# gyro_adxr.net
KiCad netlist of a schematic drawn in EAGLE
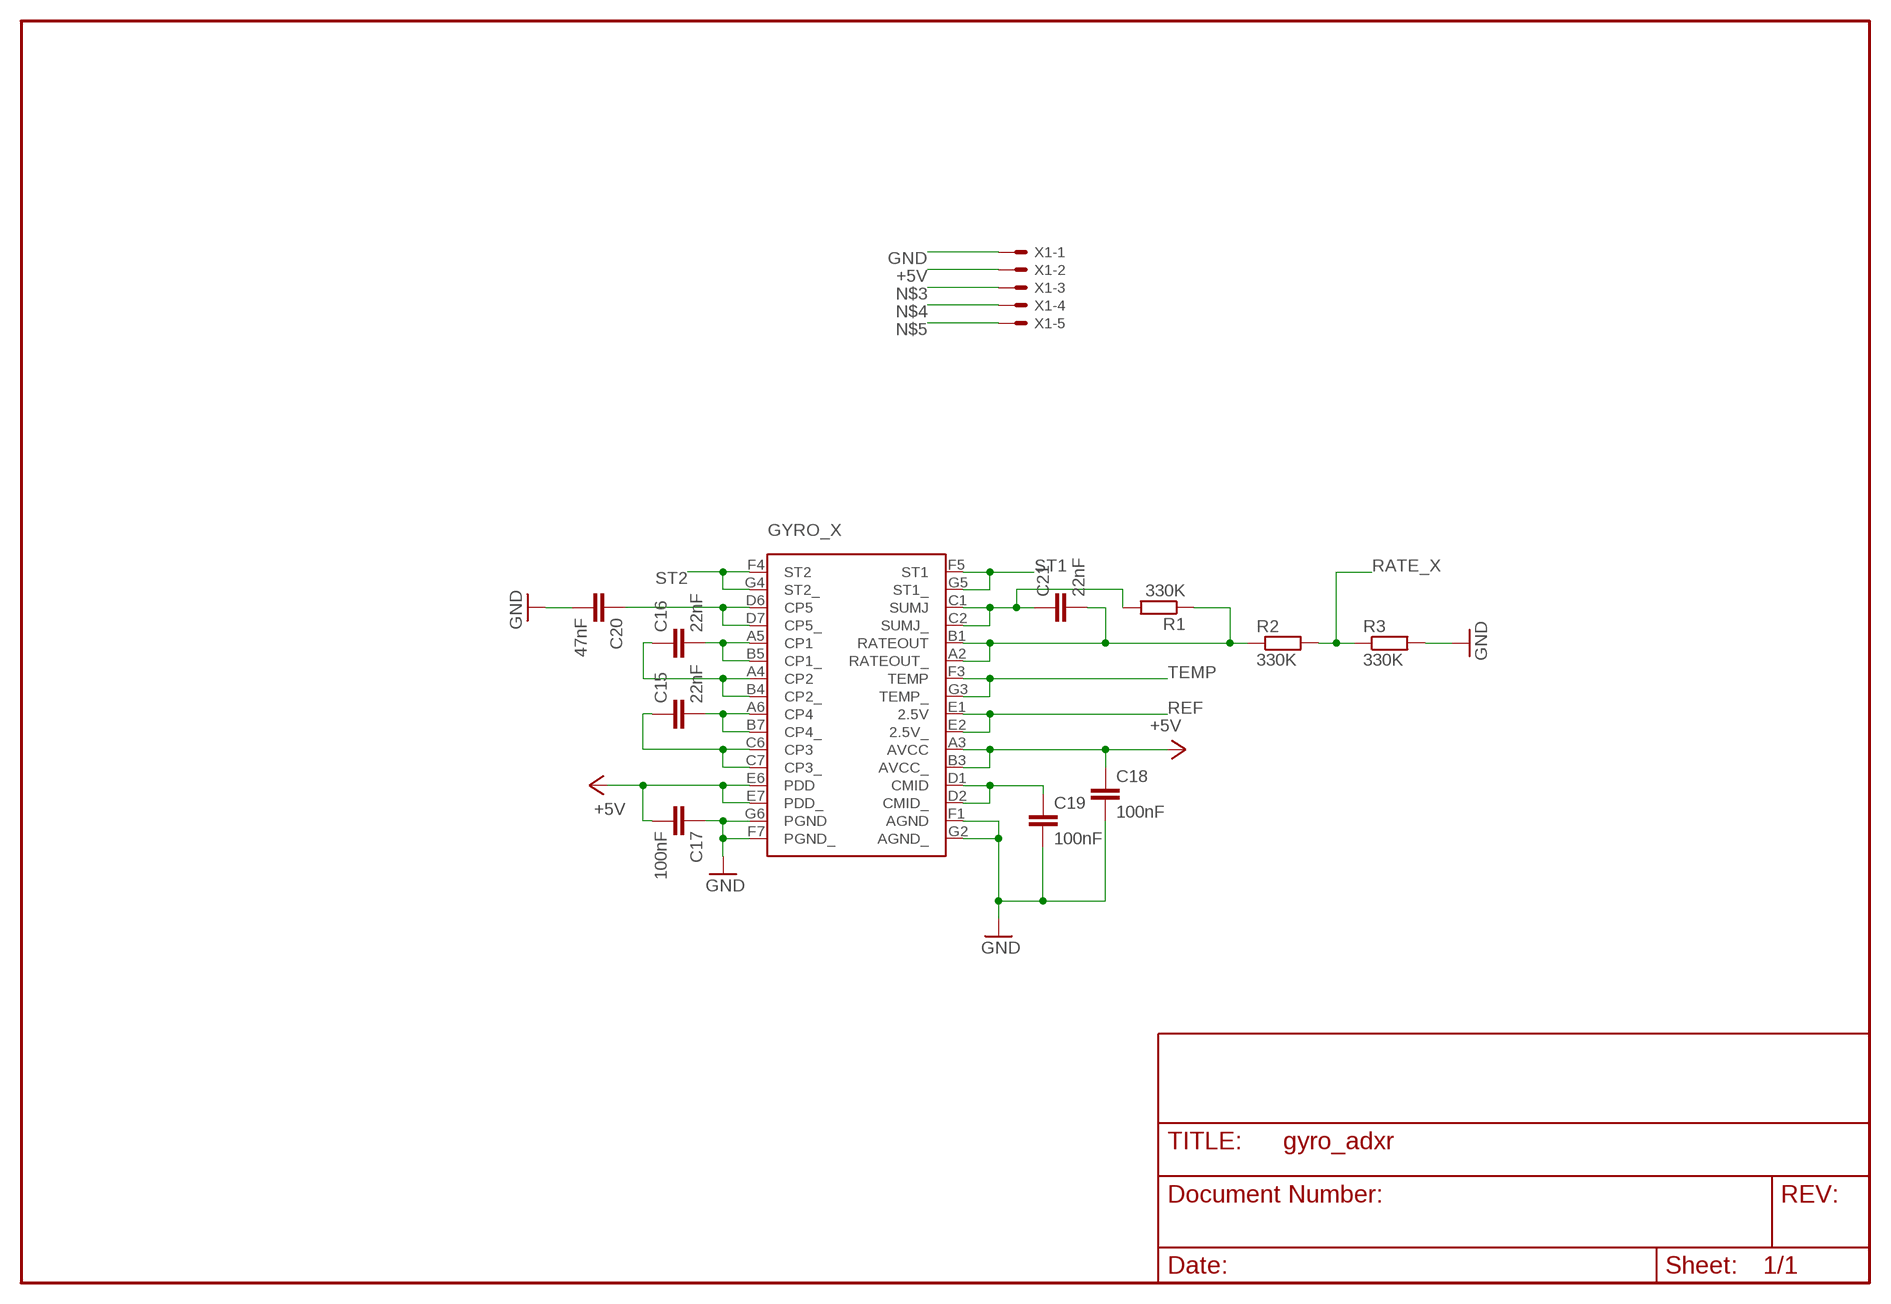
[diagram p0: schematic, sheet 1]

(export (version "E")
  (design (tool "Eeschema 10.0.6"))
  (components
    (comp (ref "C15")
      (value "22nF")
      (footprint "eagle-import:C0603K")
      (libsource (lib "eagle-import") (part "C-EUC0603K"))
    )
    (comp (ref "C16")
      (value "22nF")
      (footprint "eagle-import:C0603K")
      (libsource (lib "eagle-import") (part "C-EUC0603K"))
    )
    (comp (ref "C17")
      (value "100nF")
      (footprint "eagle-import:C0603K")
      (libsource (lib "eagle-import") (part "C-EUC0603K"))
    )
    (comp (ref "C18")
      (value "100nF")
      (footprint "eagle-import:C0603K")
      (libsource (lib "eagle-import") (part "C-EUC0603K"))
    )
    (comp (ref "C19")
      (value "100nF")
      (footprint "eagle-import:C0603K")
      (libsource (lib "eagle-import") (part "C-EUC0603K"))
    )
    (comp (ref "C20")
      (value "47nF")
      (footprint "eagle-import:C0603K")
      (libsource (lib "eagle-import") (part "C-EUC0603K"))
    )
    (comp (ref "C21")
      (value "22nF")
      (footprint "eagle-import:C0603K")
      (libsource (lib "eagle-import") (part "C-EUC0603K"))
    )
    (comp (ref "GYRO_X")
      (value "ADXR")
      (footprint "eagle-import:BC-32")
      (libsource (lib "eagle-import") (part "ADXR"))
    )
    (comp (ref "R1")
      (value "330K")
      (footprint "eagle-import:R0603")
      (libsource (lib "eagle-import") (part "R-EU_R0603"))
    )
    (comp (ref "R2")
      (value "330K")
      (footprint "eagle-import:R0603")
      (libsource (lib "eagle-import") (part "R-EU_R0603"))
    )
    (comp (ref "R3")
      (value "330K")
      (footprint "eagle-import:R0603")
      (libsource (lib "eagle-import") (part "R-EU_R0603"))
    )
    (comp (ref "X1")
      (value "53047-05")
      (footprint "eagle-import:53047-05")
      (libsource (lib "eagle-import") (part "53?-05047"))
    )
  )
  (nets
    (net (code "1") (name "+5V") (class "Default")
      (node (ref "C17") (pin "2") (pinfunction "2_2") (pintype "passive"))
      (node (ref "C18") (pin "1") (pinfunction "1_1") (pintype "passive"))
      (node (ref "GYRO_X") (pin "A3") (pinfunction "AVCC_A3") (pintype "bidirectional"))
      (node (ref "GYRO_X") (pin "B3") (pinfunction "AVCC__B3") (pintype "bidirectional"))
      (node (ref "GYRO_X") (pin "E6") (pinfunction "PDD_E6") (pintype "bidirectional"))
      (node (ref "GYRO_X") (pin "E7") (pinfunction "PDD__E7") (pintype "bidirectional"))
      (node (ref "X1") (pin "2") (pinfunction "S_2") (pintype "passive"))
    )
    (net (code "2") (name "/N$3") (class "Default")
      (node (ref "X1") (pin "3") (pinfunction "S_3") (pintype "passive"))
    )
    (net (code "3") (name "/N$4") (class "Default")
      (node (ref "X1") (pin "4") (pinfunction "S_4") (pintype "passive"))
    )
    (net (code "4") (name "/N$5") (class "Default")
      (node (ref "X1") (pin "5") (pinfunction "S_5") (pintype "passive"))
    )
    (net (code "5") (name "/RATE_X") (class "Default")
      (node (ref "R2") (pin "2") (pinfunction "2_2") (pintype "passive"))
      (node (ref "R3") (pin "1") (pinfunction "1_1") (pintype "passive"))
    )
    (net (code "6") (name "/REF") (class "Default")
      (node (ref "GYRO_X") (pin "E1") (pinfunction "2.5V_E1") (pintype "bidirectional"))
      (node (ref "GYRO_X") (pin "E2") (pinfunction "2.5V__E2") (pintype "bidirectional"))
    )
    (net (code "7") (name "/ST1") (class "Default")
      (node (ref "GYRO_X") (pin "F5") (pinfunction "ST1_F5") (pintype "bidirectional"))
      (node (ref "GYRO_X") (pin "G5") (pinfunction "ST1__G5") (pintype "bidirectional"))
    )
    (net (code "8") (name "/ST2") (class "Default")
      (node (ref "GYRO_X") (pin "F4") (pinfunction "ST2_F4") (pintype "bidirectional"))
      (node (ref "GYRO_X") (pin "G4") (pinfunction "ST2__G4") (pintype "bidirectional"))
    )
    (net (code "9") (name "/TEMP") (class "Default")
      (node (ref "GYRO_X") (pin "F3") (pinfunction "TEMP_F3") (pintype "bidirectional"))
      (node (ref "GYRO_X") (pin "G3") (pinfunction "TEMP__G3") (pintype "bidirectional"))
    )
    (net (code "10") (name "GND") (class "Default")
      (node (ref "C17") (pin "1") (pinfunction "1_1") (pintype "passive"))
      (node (ref "C18") (pin "2") (pinfunction "2_2") (pintype "passive"))
      (node (ref "C19") (pin "2") (pinfunction "2_2") (pintype "passive"))
      (node (ref "C20") (pin "2") (pinfunction "2_2") (pintype "passive"))
      (node (ref "GYRO_X") (pin "F1") (pinfunction "AGND_F1") (pintype "bidirectional"))
      (node (ref "GYRO_X") (pin "F7") (pinfunction "PGND__F7") (pintype "bidirectional"))
      (node (ref "GYRO_X") (pin "G2") (pinfunction "AGND__G2") (pintype "bidirectional"))
      (node (ref "GYRO_X") (pin "G6") (pinfunction "PGND_G6") (pintype "bidirectional"))
      (node (ref "R3") (pin "2") (pinfunction "2_2") (pintype "passive"))
      (node (ref "X1") (pin "1") (pinfunction "S_1") (pintype "passive"))
    )
    (net (code "11") (name "Net-(GYRO_X-CMID)") (class "Default")
      (node (ref "C19") (pin "1") (pinfunction "1_1") (pintype "passive"))
      (node (ref "GYRO_X") (pin "D1") (pinfunction "CMID_D1") (pintype "bidirectional"))
      (node (ref "GYRO_X") (pin "D2") (pinfunction "CMID__D2") (pintype "bidirectional"))
    )
    (net (code "12") (name "Net-(GYRO_X-CP1)") (class "Default")
      (node (ref "C16") (pin "2") (pinfunction "2_2") (pintype "passive"))
      (node (ref "GYRO_X") (pin "A5") (pinfunction "CP1_A5") (pintype "bidirectional"))
      (node (ref "GYRO_X") (pin "B5") (pinfunction "CP1__B5") (pintype "bidirectional"))
    )
    (net (code "13") (name "Net-(GYRO_X-CP2)") (class "Default")
      (node (ref "C16") (pin "1") (pinfunction "1_1") (pintype "passive"))
      (node (ref "GYRO_X") (pin "A4") (pinfunction "CP2_A4") (pintype "bidirectional"))
      (node (ref "GYRO_X") (pin "B4") (pinfunction "CP2__B4") (pintype "bidirectional"))
    )
    (net (code "14") (name "Net-(GYRO_X-CP3)") (class "Default")
      (node (ref "C15") (pin "1") (pinfunction "1_1") (pintype "passive"))
      (node (ref "GYRO_X") (pin "C6") (pinfunction "CP3_C6") (pintype "bidirectional"))
      (node (ref "GYRO_X") (pin "C7") (pinfunction "CP3__C7") (pintype "bidirectional"))
    )
    (net (code "15") (name "Net-(GYRO_X-CP4)") (class "Default")
      (node (ref "C15") (pin "2") (pinfunction "2_2") (pintype "passive"))
      (node (ref "GYRO_X") (pin "A6") (pinfunction "CP4_A6") (pintype "bidirectional"))
      (node (ref "GYRO_X") (pin "B7") (pinfunction "CP4__B7") (pintype "bidirectional"))
    )
    (net (code "16") (name "Net-(GYRO_X-CP5)") (class "Default")
      (node (ref "C20") (pin "1") (pinfunction "1_1") (pintype "passive"))
      (node (ref "GYRO_X") (pin "D6") (pinfunction "CP5_D6") (pintype "bidirectional"))
      (node (ref "GYRO_X") (pin "D7") (pinfunction "CP5__D7") (pintype "bidirectional"))
    )
    (net (code "17") (name "Net-(GYRO_X-RATEOUT)") (class "Default")
      (node (ref "C21") (pin "2") (pinfunction "2_2") (pintype "passive"))
      (node (ref "GYRO_X") (pin "A2") (pinfunction "RATEOUT__A2") (pintype "bidirectional"))
      (node (ref "GYRO_X") (pin "B1") (pinfunction "RATEOUT_B1") (pintype "bidirectional"))
      (node (ref "R1") (pin "1") (pinfunction "1_1") (pintype "passive"))
      (node (ref "R2") (pin "1") (pinfunction "1_1") (pintype "passive"))
    )
    (net (code "18") (name "Net-(GYRO_X-SUMJ)") (class "Default")
      (node (ref "C21") (pin "1") (pinfunction "1_1") (pintype "passive"))
      (node (ref "GYRO_X") (pin "C1") (pinfunction "SUMJ_C1") (pintype "bidirectional"))
      (node (ref "GYRO_X") (pin "C2") (pinfunction "SUMJ__C2") (pintype "bidirectional"))
      (node (ref "R1") (pin "2") (pinfunction "2_2") (pintype "passive"))
    )
  )
)
